# SilentStepStick-TMC2209_v20.net
KiCad netlist of a schematic drawn in EAGLE
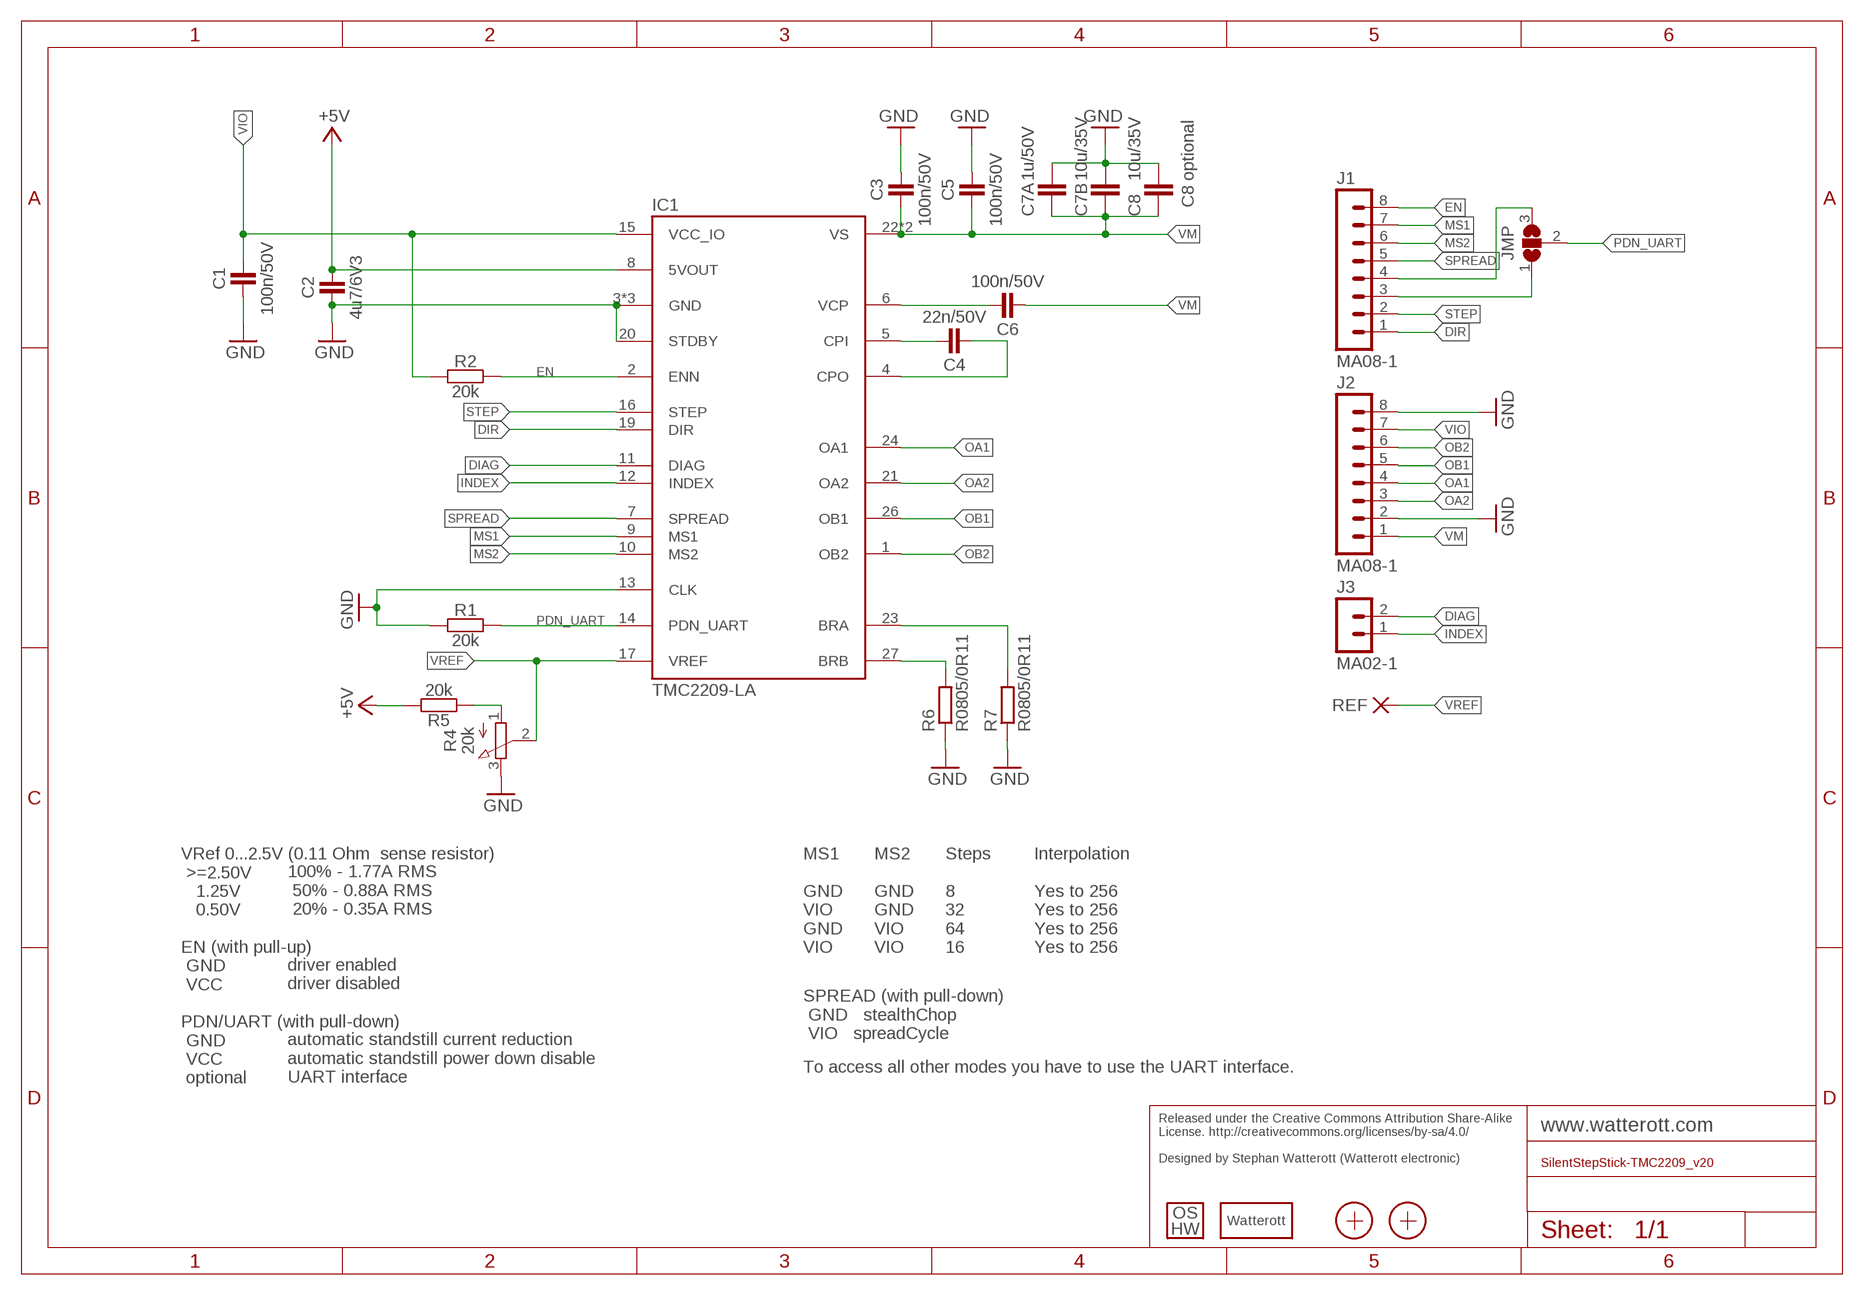
[diagram p0: schematic, sheet 1]

(export (version "E")
  (design (tool "Eeschema 10.0.6"))
  (components
    (comp (ref "C1")
      (value "100n/50V")
      (footprint "eagle-import:C0402")
      (libsource (lib "eagle-import") (part "CAPACITOR-0402"))
    )
    (comp (ref "C2")
      (value "4u7/6V3")
      (footprint "eagle-import:C0402")
      (libsource (lib "eagle-import") (part "CAPACITOR-0402"))
    )
    (comp (ref "C3")
      (value "100n/50V")
      (footprint "eagle-import:C0402")
      (libsource (lib "eagle-import") (part "CAPACITOR-0402"))
    )
    (comp (ref "C4")
      (value "22n/50V")
      (footprint "eagle-import:C0402")
      (libsource (lib "eagle-import") (part "CAPACITOR-0402"))
    )
    (comp (ref "C5")
      (value "100n/50V")
      (footprint "eagle-import:C0402")
      (libsource (lib "eagle-import") (part "CAPACITOR-0402"))
    )
    (comp (ref "C6")
      (value "100n/50V")
      (footprint "eagle-import:C0402")
      (libsource (lib "eagle-import") (part "CAPACITOR-0402"))
    )
    (comp (ref "C7A")
      (value "1u/50V")
      (footprint "eagle-import:C0805")
      (libsource (lib "eagle-import") (part "C-EUC0805"))
    )
    (comp (ref "C7B")
      (value "10u/35V")
      (footprint "eagle-import:C1206")
      (libsource (lib "eagle-import") (part "C-EUC1206"))
    )
    (comp (ref "C8")
      (value "10u/35V")
      (footprint "eagle-import:C1206")
      (libsource (lib "eagle-import") (part "C-EUC1206"))
    )
    (comp (ref "IC1")
      (value "TMC2209-LA")
      (footprint "eagle-import:QFN28-PAD3.7")
      (libsource (lib "eagle-import") (part "TMC2209-LA"))
    )
    (comp (ref "J1")
      (value "MA08-1")
      (footprint "eagle-import:MA08-1")
      (libsource (lib "eagle-import") (part "MA08-1"))
    )
    (comp (ref "J2")
      (value "MA08-1")
      (footprint "eagle-import:MA08-1")
      (libsource (lib "eagle-import") (part "MA08-1"))
    )
    (comp (ref "J3")
      (value "MA02-1")
      (footprint "eagle-import:MA02-1")
      (libsource (lib "eagle-import") (part "MA02-1"))
    )
    (comp (ref "JMP")
      (value "JUMPER3-0402-NC")
      (footprint "eagle-import:JUMPER3-0402_NC")
      (libsource (lib "eagle-import") (part "JUMPER3-0402-NC"))
    )
    (comp (ref "LOGO3")
      (value "LOGO_SPARK-2")
      (footprint "eagle-import:SPARK_2MM")
      (libsource (lib "eagle-import") (part "LOGO_SPARK-2"))
    )
    (comp (ref "LOGO4")
      (value "LOGO_OSHW-2")
      (footprint "eagle-import:OSHW_2MM")
      (libsource (lib "eagle-import") (part "LOGO_OSHW-2"))
    )
    (comp (ref "R1")
      (value "20k")
      (footprint "eagle-import:C0402")
      (libsource (lib "eagle-import") (part "RESISTOR-0402"))
    )
    (comp (ref "R2")
      (value "20k")
      (footprint "eagle-import:C0402")
      (libsource (lib "eagle-import") (part "RESISTOR-0402"))
    )
    (comp (ref "R4")
      (value "20k")
      (footprint "eagle-import:POT_EVM3R")
      (libsource (lib "eagle-import") (part "POT-EVM3R"))
    )
    (comp (ref "R5")
      (value "20k")
      (footprint "eagle-import:C0402")
      (libsource (lib "eagle-import") (part "RESISTOR-0402"))
    )
    (comp (ref "R6")
      (value "R0805/0R11")
      (footprint "eagle-import:M0805")
      (libsource (lib "eagle-import") (part "R-EU_M0805"))
    )
    (comp (ref "R7")
      (value "R0805/0R11")
      (footprint "eagle-import:M0805")
      (libsource (lib "eagle-import") (part "R-EU_M0805"))
    )
    (comp (ref "REF")
      (value "PAD-0.6-1.1")
      (footprint "eagle-import:PAD-0.6-1.1")
      (libsource (lib "eagle-import") (part "PAD-0.6-1.1"))
    )
    (comp (ref "X1")
      (value "PASSER-04")
      (footprint "eagle-import:PASSER_04MM")
      (libsource (lib "eagle-import") (part "PASSER-04"))
    )
    (comp (ref "X2")
      (value "PASSER-04")
      (footprint "eagle-import:PASSER_04MM")
      (libsource (lib "eagle-import") (part "PASSER-04"))
    )
  )
  (nets
    (net (code "1") (name "+5V") (class "Default")
      (node (ref "C2") (pin "2") (pinfunction "2_2") (pintype "passive"))
      (node (ref "IC1") (pin "8") (pinfunction "5VOUT_8") (pintype "power_in"))
      (node (ref "R5") (pin "2") (pinfunction "2_2") (pintype "passive"))
    )
    (net (code "2") (name "DIAG") (class "Default")
      (node (ref "IC1") (pin "11") (pinfunction "DIAG_11") (pintype "bidirectional"))
      (node (ref "J3") (pin "2") (pinfunction "2_2") (pintype "passive"))
    )
    (net (code "3") (name "DIR") (class "Default")
      (node (ref "IC1") (pin "19") (pinfunction "DIR_19") (pintype "bidirectional"))
      (node (ref "J1") (pin "1") (pinfunction "1_1") (pintype "passive"))
    )
    (net (code "4") (name "EN") (class "Default")
      (node (ref "IC1") (pin "2") (pinfunction "ENN_2") (pintype "bidirectional"))
      (node (ref "J1") (pin "8") (pinfunction "8_8") (pintype "passive"))
      (node (ref "R2") (pin "2") (pinfunction "2_2") (pintype "passive"))
    )
    (net (code "5") (name "GND") (class "Default")
      (node (ref "C1") (pin "1") (pinfunction "1_1") (pintype "passive"))
      (node (ref "C2") (pin "1") (pinfunction "1_1") (pintype "passive"))
      (node (ref "C3") (pin "2") (pinfunction "2_2") (pintype "passive"))
      (node (ref "C5") (pin "2") (pinfunction "2_2") (pintype "passive"))
      (node (ref "C7A") (pin "2") (pinfunction "2_2") (pintype "passive"))
      (node (ref "C7B") (pin "2") (pinfunction "2_2") (pintype "passive"))
      (node (ref "C8") (pin "2") (pinfunction "2_2") (pintype "passive"))
      (node (ref "IC1") (pin "13") (pinfunction "CLK_13") (pintype "bidirectional"))
      (node (ref "IC1") (pin "18") (pinfunction "GND_18") (pintype "power_in"))
      (node (ref "IC1") (pin "20") (pinfunction "STDBY_20") (pintype "bidirectional"))
      (node (ref "IC1") (pin "3") (pinfunction "GND_3") (pintype "power_in"))
      (node (ref "IC1") (pin "TP") (pinfunction "GND_TP") (pintype "power_in"))
      (node (ref "J2") (pin "2") (pinfunction "2_2") (pintype "passive"))
      (node (ref "J2") (pin "8") (pinfunction "8_8") (pintype "passive"))
      (node (ref "R1") (pin "1") (pinfunction "1_1") (pintype "passive"))
      (node (ref "R4") (pin "3") (pinfunction "E_3") (pintype "passive"))
      (node (ref "R6") (pin "1") (pinfunction "1_1") (pintype "passive"))
      (node (ref "R7") (pin "1") (pinfunction "1_1") (pintype "passive"))
    )
    (net (code "6") (name "INDEX") (class "Default")
      (node (ref "IC1") (pin "12") (pinfunction "INDEX_12") (pintype "bidirectional"))
      (node (ref "J3") (pin "1") (pinfunction "1_1") (pintype "passive"))
    )
    (net (code "7") (name "MS1") (class "Default")
      (node (ref "IC1") (pin "9") (pinfunction "MS1_9") (pintype "bidirectional"))
      (node (ref "J1") (pin "7") (pinfunction "7_7") (pintype "passive"))
    )
    (net (code "8") (name "MS2") (class "Default")
      (node (ref "IC1") (pin "10") (pinfunction "MS2_10") (pintype "bidirectional"))
      (node (ref "J1") (pin "6") (pinfunction "6_6") (pintype "passive"))
    )
    (net (code "9") (name "Net-(IC1-BRA)") (class "Default")
      (node (ref "IC1") (pin "23") (pinfunction "BRA_23") (pintype "output"))
      (node (ref "R7") (pin "2") (pinfunction "2_2") (pintype "passive"))
    )
    (net (code "10") (name "Net-(IC1-BRB)") (class "Default")
      (node (ref "IC1") (pin "27") (pinfunction "BRB_27") (pintype "output"))
      (node (ref "R6") (pin "2") (pinfunction "2_2") (pintype "passive"))
    )
    (net (code "11") (name "Net-(IC1-CPI)") (class "Default")
      (node (ref "C4") (pin "2") (pinfunction "2_2") (pintype "passive"))
      (node (ref "IC1") (pin "5") (pinfunction "CPI_5") (pintype "passive"))
    )
    (net (code "12") (name "Net-(IC1-CPO)") (class "Default")
      (node (ref "C4") (pin "1") (pinfunction "1_1") (pintype "passive"))
      (node (ref "IC1") (pin "4") (pinfunction "CPO_4") (pintype "passive"))
    )
    (net (code "13") (name "Net-(IC1-VCP)") (class "Default")
      (node (ref "C6") (pin "2") (pinfunction "2_2") (pintype "passive"))
      (node (ref "IC1") (pin "6") (pinfunction "VCP_6") (pintype "passive"))
    )
    (net (code "14") (name "Net-(J1-Pad3)") (class "Default")
      (node (ref "J1") (pin "3") (pinfunction "3_3") (pintype "passive"))
      (node (ref "JMP") (pin "1") (pinfunction "1_1") (pintype "passive"))
    )
    (net (code "15") (name "Net-(J1-Pad4)") (class "Default")
      (node (ref "J1") (pin "4") (pinfunction "4_4") (pintype "passive"))
      (node (ref "JMP") (pin "3") (pinfunction "3_3") (pintype "passive"))
    )
    (net (code "16") (name "Net-(R4-A)") (class "Default")
      (node (ref "R4") (pin "1") (pinfunction "A_1") (pintype "passive"))
      (node (ref "R5") (pin "1") (pinfunction "1_1") (pintype "passive"))
    )
    (net (code "17") (name "OA1") (class "Default")
      (node (ref "IC1") (pin "24") (pinfunction "OA1_24") (pintype "output"))
      (node (ref "J2") (pin "4") (pinfunction "4_4") (pintype "passive"))
    )
    (net (code "18") (name "OA2") (class "Default")
      (node (ref "IC1") (pin "21") (pinfunction "OA2_21") (pintype "output"))
      (node (ref "J2") (pin "3") (pinfunction "3_3") (pintype "passive"))
    )
    (net (code "19") (name "OB1") (class "Default")
      (node (ref "IC1") (pin "26") (pinfunction "OB1_26") (pintype "output"))
      (node (ref "J2") (pin "5") (pinfunction "5_5") (pintype "passive"))
    )
    (net (code "20") (name "OB2") (class "Default")
      (node (ref "IC1") (pin "1") (pinfunction "OB2_1") (pintype "output"))
      (node (ref "J2") (pin "6") (pinfunction "6_6") (pintype "passive"))
    )
    (net (code "21") (name "PDN_UART") (class "Default")
      (node (ref "IC1") (pin "14") (pinfunction "PDN_UART_14") (pintype "bidirectional"))
      (node (ref "JMP") (pin "2") (pinfunction "2_2") (pintype "passive"))
      (node (ref "R1") (pin "2") (pinfunction "2_2") (pintype "passive"))
    )
    (net (code "22") (name "SPREAD") (class "Default")
      (node (ref "IC1") (pin "7") (pinfunction "SPREAD_7") (pintype "bidirectional"))
      (node (ref "J1") (pin "5") (pinfunction "5_5") (pintype "passive"))
    )
    (net (code "23") (name "STEP") (class "Default")
      (node (ref "IC1") (pin "16") (pinfunction "STEP_16") (pintype "bidirectional"))
      (node (ref "J1") (pin "2") (pinfunction "2_2") (pintype "passive"))
    )
    (net (code "24") (name "VIO") (class "Default")
      (node (ref "C1") (pin "2") (pinfunction "2_2") (pintype "passive"))
      (node (ref "IC1") (pin "15") (pinfunction "VCC_IO_15") (pintype "power_in"))
      (node (ref "J2") (pin "7") (pinfunction "7_7") (pintype "passive"))
      (node (ref "R2") (pin "1") (pinfunction "1_1") (pintype "passive"))
    )
    (net (code "25") (name "VM") (class "Default")
      (node (ref "C3") (pin "1") (pinfunction "1_1") (pintype "passive"))
      (node (ref "C5") (pin "1") (pinfunction "1_1") (pintype "passive"))
      (node (ref "C6") (pin "1") (pinfunction "1_1") (pintype "passive"))
      (node (ref "C7A") (pin "1") (pinfunction "1_1") (pintype "passive"))
      (node (ref "C7B") (pin "1") (pinfunction "1_1") (pintype "passive"))
      (node (ref "C8") (pin "1") (pinfunction "1_1") (pintype "passive"))
      (node (ref "IC1") (pin "22") (pinfunction "VS_22") (pintype "power_in"))
      (node (ref "IC1") (pin "28") (pinfunction "VS_28") (pintype "power_in"))
      (node (ref "J2") (pin "1") (pinfunction "1_1") (pintype "passive"))
    )
    (net (code "26") (name "VREF") (class "Default")
      (node (ref "IC1") (pin "17") (pinfunction "VREF_17") (pintype "passive"))
      (node (ref "R4") (pin "2") (pinfunction "S_2") (pintype "passive"))
      (node (ref "REF") (pin "1") (pinfunction "P_1") (pintype "passive"))
    )
  )
)
